# VoiceInterface.net
KiCad netlist of a schematic drawn in EAGLE
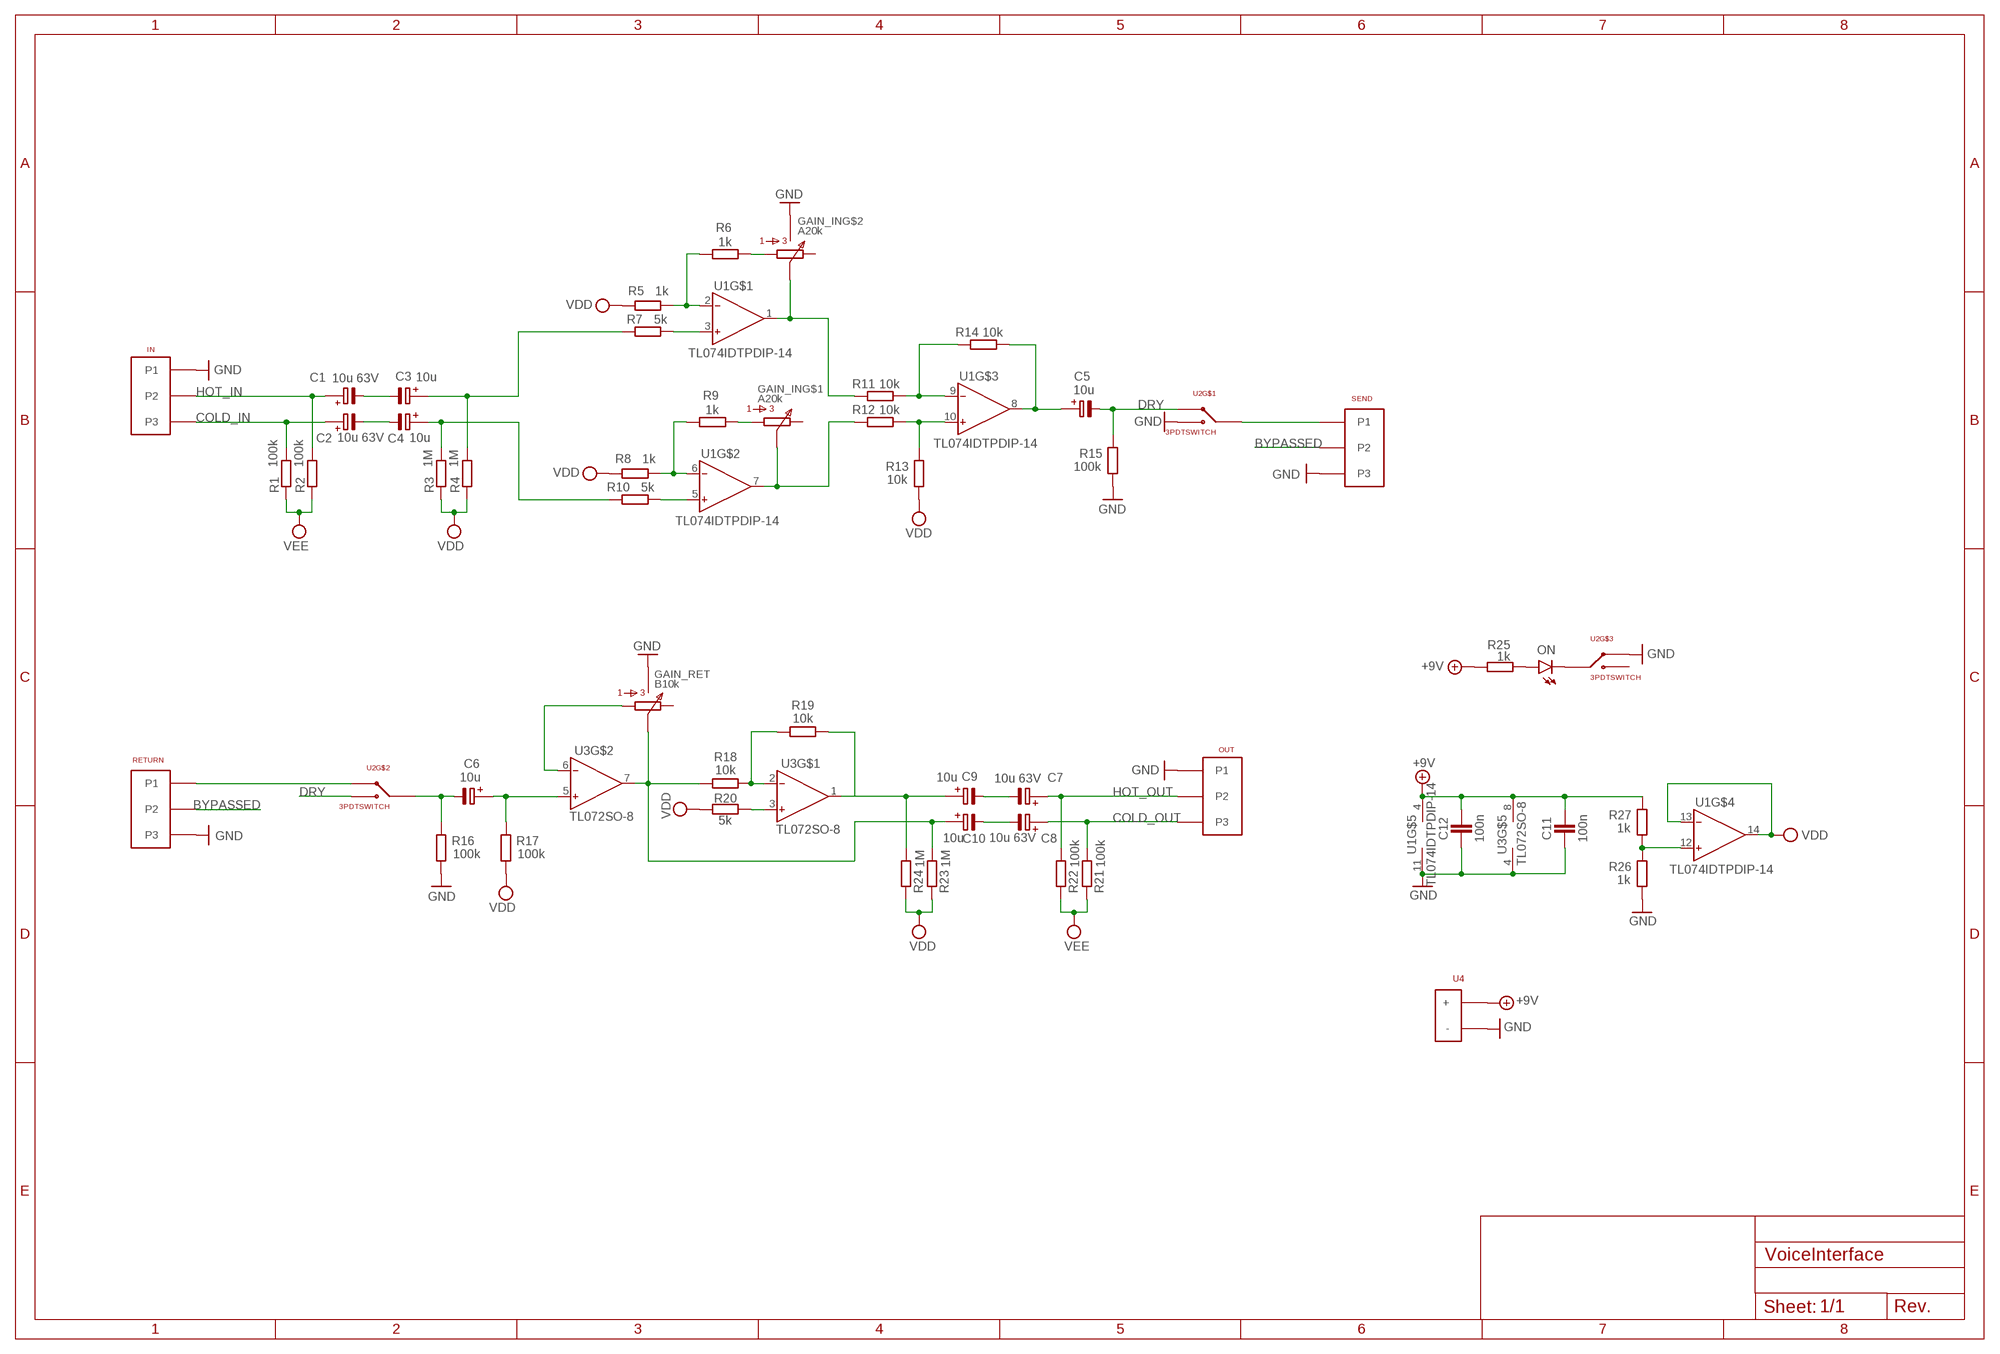
[diagram p0: schematic, sheet 1]

(export (version "E")
  (design (tool "Eeschema 10.0.6"))
  (components
    (comp (ref "C1")
      (value "10u 63V")
      (footprint "eagle-import:UD-8X10_NICHICON")
      (libsource (lib "eagle-import") (part "ELECT_CAPACITORCAP10"))
    )
    (comp (ref "C2")
      (value "10u 63V")
      (footprint "eagle-import:UD-8X10_NICHICON")
      (libsource (lib "eagle-import") (part "ELECT_CAPACITORCAP10"))
    )
    (comp (ref "C3")
      (value "10u")
      (footprint "eagle-import:UD-4X5,8_NICHICON")
      (libsource (lib "eagle-import") (part "ELECT_CAPACITORCAP6"))
    )
    (comp (ref "C4")
      (value "10u")
      (footprint "eagle-import:UD-4X5,8_NICHICON")
      (libsource (lib "eagle-import") (part "ELECT_CAPACITORCAP6"))
    )
    (comp (ref "C5")
      (value "10u")
      (footprint "eagle-import:UD-4X5,8_NICHICON")
      (libsource (lib "eagle-import") (part "ELECT_CAPACITORCAP6"))
    )
    (comp (ref "C6")
      (value "10u")
      (footprint "eagle-import:UD-4X5,8_NICHICON")
      (libsource (lib "eagle-import") (part "ELECT_CAPACITORCAP6"))
    )
    (comp (ref "C7")
      (value "10u 63V")
      (footprint "eagle-import:UD-8X10_NICHICON")
      (libsource (lib "eagle-import") (part "ELECT_CAPACITORCAP10"))
    )
    (comp (ref "C8")
      (value "10u 63V")
      (footprint "eagle-import:UD-8X10_NICHICON")
      (libsource (lib "eagle-import") (part "ELECT_CAPACITORCAP10"))
    )
    (comp (ref "C9")
      (value "10u")
      (footprint "eagle-import:UD-4X5,8_NICHICON")
      (libsource (lib "eagle-import") (part "ELECT_CAPACITORCAP6"))
    )
    (comp (ref "C10")
      (value "10u")
      (footprint "eagle-import:UD-4X5,8_NICHICON")
      (libsource (lib "eagle-import") (part "ELECT_CAPACITORCAP6"))
    )
    (comp (ref "C11")
      (value "100n")
      (footprint "eagle-import:0603")
      (libsource (lib "eagle-import") (part "CAPACITORC-0603"))
    )
    (comp (ref "C12")
      (value "100n")
      (footprint "eagle-import:0603")
      (libsource (lib "eagle-import") (part "CAPACITORC-0603"))
    )
    (comp (ref "GAIN_IN")
      (value "A20k")
      (footprint "eagle-import:P0925N")
      (fields (field (name "MPN") "P0925N-FC20AR100K"))
      (libsource (lib "eagle-import") (part "STEREO_POT"))
    )
    (comp (ref "GAIN_RET")
      (value "B10k")
      (footprint "eagle-import:P0915N")
      (fields (field (name "MPN") "P0915N-QC15AR100K"))
      (libsource (lib "eagle-import") (part "POT"))
    )
    (comp (ref "IN")
      (value "3_PIN_PORT")
      (footprint "eagle-import:3_PIN_PORT")
      (libsource (lib "eagle-import") (part "3_PIN_PORT"))
    )
    (comp (ref "ON")
      (value "LEDLED_THROUGH")
      (footprint "eagle-import:LED3MM")
      (libsource (lib "eagle-import") (part "LEDLED_THROUGH"))
    )
    (comp (ref "OUT")
      (value "3_PIN_PORT")
      (footprint "eagle-import:3_PIN_PORT")
      (libsource (lib "eagle-import") (part "3_PIN_PORT"))
    )
    (comp (ref "R1")
      (value "100k")
      (footprint "eagle-import:R0603")
      (libsource (lib "eagle-import") (part "RESISTOR"))
    )
    (comp (ref "R2")
      (value "100k")
      (footprint "eagle-import:R0603")
      (libsource (lib "eagle-import") (part "RESISTOR"))
    )
    (comp (ref "R3")
      (value "1M")
      (footprint "eagle-import:R0603")
      (libsource (lib "eagle-import") (part "RESISTOR"))
    )
    (comp (ref "R4")
      (value "1M")
      (footprint "eagle-import:R0603")
      (libsource (lib "eagle-import") (part "RESISTOR"))
    )
    (comp (ref "R5")
      (value "1k")
      (footprint "eagle-import:R0603")
      (libsource (lib "eagle-import") (part "RESISTOR"))
    )
    (comp (ref "R6")
      (value "1k")
      (footprint "eagle-import:R0603")
      (libsource (lib "eagle-import") (part "RESISTOR"))
    )
    (comp (ref "R7")
      (value "5k")
      (footprint "eagle-import:R0603")
      (libsource (lib "eagle-import") (part "RESISTOR"))
    )
    (comp (ref "R8")
      (value "1k")
      (footprint "eagle-import:R0603")
      (libsource (lib "eagle-import") (part "RESISTOR"))
    )
    (comp (ref "R9")
      (value "1k")
      (footprint "eagle-import:R0603")
      (libsource (lib "eagle-import") (part "RESISTOR"))
    )
    (comp (ref "R10")
      (value "5k")
      (footprint "eagle-import:R0603")
      (libsource (lib "eagle-import") (part "RESISTOR"))
    )
    (comp (ref "R11")
      (value "10k")
      (footprint "eagle-import:R0603")
      (libsource (lib "eagle-import") (part "RESISTOR"))
    )
    (comp (ref "R12")
      (value "10k")
      (footprint "eagle-import:R0603")
      (libsource (lib "eagle-import") (part "RESISTOR"))
    )
    (comp (ref "R13")
      (value "10k")
      (footprint "eagle-import:R0603")
      (libsource (lib "eagle-import") (part "RESISTOR"))
    )
    (comp (ref "R14")
      (value "10k")
      (footprint "eagle-import:R0603")
      (libsource (lib "eagle-import") (part "RESISTOR"))
    )
    (comp (ref "R15")
      (value "100k")
      (footprint "eagle-import:R0603")
      (libsource (lib "eagle-import") (part "RESISTOR"))
    )
    (comp (ref "R16")
      (value "100k")
      (footprint "eagle-import:R0603")
      (libsource (lib "eagle-import") (part "RESISTOR"))
    )
    (comp (ref "R17")
      (value "100k")
      (footprint "eagle-import:R0603")
      (libsource (lib "eagle-import") (part "RESISTOR"))
    )
    (comp (ref "R18")
      (value "10k")
      (footprint "eagle-import:R0603")
      (libsource (lib "eagle-import") (part "RESISTOR"))
    )
    (comp (ref "R19")
      (value "10k")
      (footprint "eagle-import:R0603")
      (libsource (lib "eagle-import") (part "RESISTOR"))
    )
    (comp (ref "R20")
      (value "5k")
      (footprint "eagle-import:R0603")
      (libsource (lib "eagle-import") (part "RESISTOR"))
    )
    (comp (ref "R21")
      (value "100k")
      (footprint "eagle-import:R0603")
      (libsource (lib "eagle-import") (part "RESISTOR"))
    )
    (comp (ref "R22")
      (value "100k")
      (footprint "eagle-import:R0603")
      (libsource (lib "eagle-import") (part "RESISTOR"))
    )
    (comp (ref "R23")
      (value "1M")
      (footprint "eagle-import:R0603")
      (libsource (lib "eagle-import") (part "RESISTOR"))
    )
    (comp (ref "R24")
      (value "1M")
      (footprint "eagle-import:R0603")
      (libsource (lib "eagle-import") (part "RESISTOR"))
    )
    (comp (ref "R25")
      (value "1k")
      (footprint "eagle-import:R0603")
      (libsource (lib "eagle-import") (part "RESISTOR"))
    )
    (comp (ref "R26")
      (value "1k")
      (footprint "eagle-import:R0603")
      (libsource (lib "eagle-import") (part "RESISTOR"))
    )
    (comp (ref "R27")
      (value "1k")
      (footprint "eagle-import:R0603")
      (libsource (lib "eagle-import") (part "RESISTOR"))
    )
    (comp (ref "RETURN")
      (value "3_PIN_PORT")
      (footprint "eagle-import:3_PIN_PORT")
      (libsource (lib "eagle-import") (part "3_PIN_PORT"))
    )
    (comp (ref "SEND")
      (value "3_PIN_PORT")
      (footprint "eagle-import:3_PIN_PORT")
      (libsource (lib "eagle-import") (part "3_PIN_PORT"))
    )
    (comp (ref "U1")
      (value "TL074IDTPDIP-14")
      (footprint "eagle-import:DIP762W53P254L1969H508Q14B")
      (fields (field (name "MPN") "TL074CN"))
      (libsource (lib "eagle-import") (part "library_TL074IDTPDIP-14"))
    )
    (comp (ref "U2")
      (value "3PDTSWITCH")
      (footprint "eagle-import:FS57003PLT2B2M1QE")
      (fields (field (name "MPN") "FS57003PLT2B2M1QE"))
      (libsource (lib "eagle-import") (part "3PDTSWITCH"))
    )
    (comp (ref "U3")
      (value "TL072SO-8")
      (footprint "eagle-import:SOIC127P600X175-8N")
      (libsource (lib "eagle-import") (part "TL072SO-8"))
    )
    (comp (ref "U4")
      (value "POWER")
      (footprint "eagle-import:POWER")
      (libsource (lib "eagle-import") (part "POWER"))
    )
  )
  (nets
    (net (code "1") (name "+9V") (class "Default")
      (node (ref "C11") (pin "2") (pinfunction "2_2") (pintype "passive"))
      (node (ref "C12") (pin "2") (pinfunction "2_2") (pintype "passive"))
      (node (ref "R25") (pin "2") (pinfunction "2_2") (pintype "passive"))
      (node (ref "R27") (pin "1") (pinfunction "1_1") (pintype "passive"))
      (node (ref "U1") (pin "4") (pinfunction "V+_4") (pintype "power_in"))
      (node (ref "U3") (pin "8") (pinfunction "V+_8") (pintype "power_in"))
      (node (ref "U4") (pin "P$1") (pinfunction "+_P$1") (pintype "power_in"))
    )
    (net (code "2") (name "/BYPASSED") (class "Default")
      (node (ref "RETURN") (pin "P$2") (pinfunction "P2_P$2") (pintype "bidirectional"))
      (node (ref "SEND") (pin "P$2") (pinfunction "P2_P$2") (pintype "bidirectional"))
    )
    (net (code "3") (name "/COLD_IN") (class "Default")
      (node (ref "C2") (pin "+") (pinfunction "+_+") (pintype "passive"))
      (node (ref "IN") (pin "P$3") (pinfunction "P3_P$3") (pintype "bidirectional"))
      (node (ref "R1") (pin "2") (pinfunction "2_2") (pintype "passive"))
    )
    (net (code "4") (name "/COLD_OUT") (class "Default")
      (node (ref "C8") (pin "+") (pinfunction "+_+") (pintype "passive"))
      (node (ref "OUT") (pin "P$3") (pinfunction "P3_P$3") (pintype "bidirectional"))
      (node (ref "R21") (pin "2") (pinfunction "2_2") (pintype "passive"))
    )
    (net (code "5") (name "/DRY") (class "Default")
      (node (ref "C5") (pin "-") (pinfunction "-_-") (pintype "passive"))
      (node (ref "R15") (pin "1") (pinfunction "1_1") (pintype "passive"))
      (node (ref "U2") (pin "P$1") (pinfunction "1_P$1") (pintype "bidirectional"))
      (node (ref "U2") (pin "P$6") (pinfunction "3_P$6") (pintype "bidirectional"))
    )
    (net (code "6") (name "/HOT_IN") (class "Default")
      (node (ref "C1") (pin "+") (pinfunction "+_+") (pintype "passive"))
      (node (ref "IN") (pin "P$2") (pinfunction "P2_P$2") (pintype "bidirectional"))
      (node (ref "R2") (pin "2") (pinfunction "2_2") (pintype "passive"))
    )
    (net (code "7") (name "/HOT_OUT") (class "Default")
      (node (ref "C7") (pin "+") (pinfunction "+_+") (pintype "passive"))
      (node (ref "OUT") (pin "P$2") (pinfunction "P2_P$2") (pintype "bidirectional"))
      (node (ref "R22") (pin "2") (pinfunction "2_2") (pintype "passive"))
    )
    (net (code "8") (name "GND") (class "Default")
      (node (ref "C11") (pin "1") (pinfunction "1_1") (pintype "passive"))
      (node (ref "C12") (pin "1") (pinfunction "1_1") (pintype "passive"))
      (node (ref "GAIN_IN") (pin "P$7") (pinfunction "P$1_P$7") (pintype "bidirectional"))
      (node (ref "GAIN_IN") (pin "P$8") (pinfunction "P$1_P$8") (pintype "bidirectional"))
      (node (ref "GAIN_RET") (pin "P$7") (pinfunction "P$1_P$7") (pintype "bidirectional"))
      (node (ref "GAIN_RET") (pin "P$8") (pinfunction "P$1_P$8") (pintype "bidirectional"))
      (node (ref "IN") (pin "P$1") (pinfunction "P1_P$1") (pintype "bidirectional"))
      (node (ref "OUT") (pin "P$1") (pinfunction "P1_P$1") (pintype "bidirectional"))
      (node (ref "R15") (pin "2") (pinfunction "2_2") (pintype "passive"))
      (node (ref "R16") (pin "2") (pinfunction "2_2") (pintype "passive"))
      (node (ref "R26") (pin "2") (pinfunction "2_2") (pintype "passive"))
      (node (ref "RETURN") (pin "P$3") (pinfunction "P3_P$3") (pintype "bidirectional"))
      (node (ref "SEND") (pin "P$3") (pinfunction "P3_P$3") (pintype "bidirectional"))
      (node (ref "U1") (pin "11") (pinfunction "V-_11") (pintype "power_in"))
      (node (ref "U2") (pin "P$3") (pinfunction "3_P$3") (pintype "bidirectional"))
      (node (ref "U2") (pin "P$7") (pinfunction "1_P$7") (pintype "bidirectional"))
      (node (ref "U3") (pin "4") (pinfunction "V-_4") (pintype "power_in"))
      (node (ref "U4") (pin "P$2") (pinfunction "-_P$2") (pintype "power_in"))
    )
    (net (code "9") (name "Net-(C1-Pad-)") (class "Default")
      (node (ref "C1") (pin "-") (pinfunction "-_-") (pintype "passive"))
      (node (ref "C3") (pin "-") (pinfunction "-_-") (pintype "passive"))
    )
    (net (code "10") (name "Net-(C2-Pad-)") (class "Default")
      (node (ref "C2") (pin "-") (pinfunction "-_-") (pintype "passive"))
      (node (ref "C4") (pin "-") (pinfunction "-_-") (pintype "passive"))
    )
    (net (code "11") (name "Net-(C3-Pad+)") (class "Default")
      (node (ref "C3") (pin "+") (pinfunction "+_+") (pintype "passive"))
      (node (ref "R4") (pin "2") (pinfunction "2_2") (pintype "passive"))
      (node (ref "R7") (pin "2") (pinfunction "2_2") (pintype "passive"))
    )
    (net (code "12") (name "Net-(C4-Pad+)") (class "Default")
      (node (ref "C4") (pin "+") (pinfunction "+_+") (pintype "passive"))
      (node (ref "R10") (pin "2") (pinfunction "2_2") (pintype "passive"))
      (node (ref "R3") (pin "2") (pinfunction "2_2") (pintype "passive"))
    )
    (net (code "13") (name "Net-(C7-Pad-)") (class "Default")
      (node (ref "C7") (pin "-") (pinfunction "-_-") (pintype "passive"))
      (node (ref "C9") (pin "-") (pinfunction "-_-") (pintype "passive"))
    )
    (net (code "14") (name "Net-(C10-Pad-)") (class "Default")
      (node (ref "C10") (pin "-") (pinfunction "-_-") (pintype "passive"))
      (node (ref "C8") (pin "-") (pinfunction "-_-") (pintype "passive"))
    )
    (net (code "15") (name "Net-(GAIN_INA-1)") (class "Default")
      (node (ref "GAIN_IN") (pin "P$1") (pinfunction "1_P$1") (pintype "passive"))
      (node (ref "R9") (pin "1") (pinfunction "1_1") (pintype "passive"))
    )
    (net (code "16") (name "Net-(GAIN_INA-2)") (class "Default")
      (node (ref "GAIN_IN") (pin "P$2") (pinfunction "2_P$2") (pintype "passive"))
      (node (ref "R12") (pin "2") (pinfunction "2_2") (pintype "passive"))
      (node (ref "U1") (pin "7") (pinfunction "OUT_7") (pintype "output"))
    )
    (net (code "17") (name "Net-(GAIN_INB-1)") (class "Default")
      (node (ref "GAIN_IN") (pin "P$4") (pinfunction "1_P$4") (pintype "passive"))
      (node (ref "R6") (pin "1") (pinfunction "1_1") (pintype "passive"))
    )
    (net (code "18") (name "Net-(GAIN_INB-2)") (class "Default")
      (node (ref "GAIN_IN") (pin "P$5") (pinfunction "2_P$5") (pintype "passive"))
      (node (ref "R11") (pin "2") (pinfunction "2_2") (pintype "passive"))
      (node (ref "U1") (pin "1") (pinfunction "OUT_1") (pintype "output"))
    )
    (net (code "19") (name "Net-(GAIN_RET-1)") (class "Default")
      (node (ref "GAIN_RET") (pin "P$1") (pinfunction "1_P$1") (pintype "passive"))
      (node (ref "U3") (pin "6") (pinfunction "IN-_6") (pintype "input"))
    )
    (net (code "20") (name "Net-(GAIN_RET-2)") (class "Default")
      (node (ref "C10") (pin "+") (pinfunction "+_+") (pintype "passive"))
      (node (ref "GAIN_RET") (pin "P$2") (pinfunction "2_P$2") (pintype "passive"))
      (node (ref "R18") (pin "2") (pinfunction "2_2") (pintype "passive"))
      (node (ref "R23") (pin "2") (pinfunction "2_2") (pintype "passive"))
      (node (ref "U3") (pin "7") (pinfunction "OUT_7") (pintype "output"))
    )
    (net (code "21") (name "Net-(ON-C)") (class "Default")
      (node (ref "ON") (pin "K") (pinfunction "C_K") (pintype "passive"))
      (node (ref "U2") (pin "P$8") (pinfunction "2_P$8") (pintype "bidirectional"))
    )
    (net (code "22") (name "Net-(ON-PadA)") (class "Default")
      (node (ref "ON") (pin "A") (pinfunction "A_A") (pintype "passive"))
      (node (ref "R25") (pin "1") (pinfunction "1_1") (pintype "passive"))
    )
    (net (code "23") (name "Net-(RETURN-P1)") (class "Default")
      (node (ref "RETURN") (pin "P$1") (pinfunction "P1_P$1") (pintype "bidirectional"))
      (node (ref "U2") (pin "P$4") (pinfunction "1_P$4") (pintype "bidirectional"))
    )
    (net (code "24") (name "Net-(SEND-P1)") (class "Default")
      (node (ref "SEND") (pin "P$1") (pinfunction "P1_P$1") (pintype "bidirectional"))
      (node (ref "U2") (pin "P$2") (pinfunction "2_P$2") (pintype "bidirectional"))
    )
    (net (code "25") (name "Net-(U1A-IN+)") (class "Default")
      (node (ref "R7") (pin "1") (pinfunction "1_1") (pintype "passive"))
      (node (ref "U1") (pin "3") (pinfunction "IN+_3") (pintype "input"))
    )
    (net (code "26") (name "Net-(U1A-IN-)") (class "Default")
      (node (ref "R5") (pin "1") (pinfunction "1_1") (pintype "passive"))
      (node (ref "R6") (pin "2") (pinfunction "2_2") (pintype "passive"))
      (node (ref "U1") (pin "2") (pinfunction "IN-_2") (pintype "input"))
    )
    (net (code "27") (name "Net-(U1B-IN+)") (class "Default")
      (node (ref "R10") (pin "1") (pinfunction "1_1") (pintype "passive"))
      (node (ref "U1") (pin "5") (pinfunction "IN+_5") (pintype "input"))
    )
    (net (code "28") (name "Net-(U1B-IN-)") (class "Default")
      (node (ref "R8") (pin "1") (pinfunction "1_1") (pintype "passive"))
      (node (ref "R9") (pin "2") (pinfunction "2_2") (pintype "passive"))
      (node (ref "U1") (pin "6") (pinfunction "IN-_6") (pintype "input"))
    )
    (net (code "29") (name "Net-(U1C-IN+)") (class "Default")
      (node (ref "R12") (pin "1") (pinfunction "1_1") (pintype "passive"))
      (node (ref "R13") (pin "1") (pinfunction "1_1") (pintype "passive"))
      (node (ref "U1") (pin "10") (pinfunction "IN+_10") (pintype "input"))
    )
    (net (code "30") (name "Net-(U1C-IN-)") (class "Default")
      (node (ref "R11") (pin "1") (pinfunction "1_1") (pintype "passive"))
      (node (ref "R14") (pin "2") (pinfunction "2_2") (pintype "passive"))
      (node (ref "U1") (pin "9") (pinfunction "IN-_9") (pintype "input"))
    )
    (net (code "31") (name "Net-(U1C-OUT)") (class "Default")
      (node (ref "C5") (pin "+") (pinfunction "+_+") (pintype "passive"))
      (node (ref "R14") (pin "1") (pinfunction "1_1") (pintype "passive"))
      (node (ref "U1") (pin "8") (pinfunction "OUT_8") (pintype "output"))
    )
    (net (code "32") (name "Net-(U1D-IN+)") (class "Default")
      (node (ref "R26") (pin "1") (pinfunction "1_1") (pintype "passive"))
      (node (ref "R27") (pin "2") (pinfunction "2_2") (pintype "passive"))
      (node (ref "U1") (pin "12") (pinfunction "IN+_12") (pintype "input"))
    )
    (net (code "33") (name "Net-(U2B-2)") (class "Default")
      (node (ref "C6") (pin "-") (pinfunction "-_-") (pintype "passive"))
      (node (ref "R16") (pin "1") (pinfunction "1_1") (pintype "passive"))
      (node (ref "U2") (pin "P$5") (pinfunction "2_P$5") (pintype "bidirectional"))
    )
    (net (code "34") (name "Net-(U3A-IN+)") (class "Default")
      (node (ref "R20") (pin "1") (pinfunction "1_1") (pintype "passive"))
      (node (ref "U3") (pin "3") (pinfunction "IN+_3") (pintype "input"))
    )
    (net (code "35") (name "Net-(U3A-IN-)") (class "Default")
      (node (ref "R18") (pin "1") (pinfunction "1_1") (pintype "passive"))
      (node (ref "R19") (pin "2") (pinfunction "2_2") (pintype "passive"))
      (node (ref "U3") (pin "2") (pinfunction "IN-_2") (pintype "input"))
    )
    (net (code "36") (name "Net-(U3A-OUT)") (class "Default")
      (node (ref "C9") (pin "+") (pinfunction "+_+") (pintype "passive"))
      (node (ref "R19") (pin "1") (pinfunction "1_1") (pintype "passive"))
      (node (ref "R24") (pin "2") (pinfunction "2_2") (pintype "passive"))
      (node (ref "U3") (pin "1") (pinfunction "OUT_1") (pintype "output"))
    )
    (net (code "37") (name "Net-(U3B-IN+)") (class "Default")
      (node (ref "C6") (pin "+") (pinfunction "+_+") (pintype "passive"))
      (node (ref "R17") (pin "1") (pinfunction "1_1") (pintype "passive"))
      (node (ref "U3") (pin "5") (pinfunction "IN+_5") (pintype "input"))
    )
    (net (code "38") (name "VDD") (class "Default")
      (node (ref "R13") (pin "2") (pinfunction "2_2") (pintype "passive"))
      (node (ref "R17") (pin "2") (pinfunction "2_2") (pintype "passive"))
      (node (ref "R20") (pin "2") (pinfunction "2_2") (pintype "passive"))
      (node (ref "R23") (pin "1") (pinfunction "1_1") (pintype "passive"))
      (node (ref "R24") (pin "1") (pinfunction "1_1") (pintype "passive"))
      (node (ref "R3") (pin "1") (pinfunction "1_1") (pintype "passive"))
      (node (ref "R4") (pin "1") (pinfunction "1_1") (pintype "passive"))
      (node (ref "R5") (pin "2") (pinfunction "2_2") (pintype "passive"))
      (node (ref "R8") (pin "2") (pinfunction "2_2") (pintype "passive"))
      (node (ref "U1") (pin "13") (pinfunction "IN-_13") (pintype "input"))
      (node (ref "U1") (pin "14") (pinfunction "OUT_14") (pintype "output"))
    )
    (net (code "39") (name "VEE") (class "Default")
      (node (ref "R1") (pin "1") (pinfunction "1_1") (pintype "passive"))
      (node (ref "R2") (pin "1") (pinfunction "1_1") (pintype "passive"))
      (node (ref "R21") (pin "1") (pinfunction "1_1") (pintype "passive"))
      (node (ref "R22") (pin "1") (pinfunction "1_1") (pintype "passive"))
    )
    (net (code "40") (name "unconnected-(GAIN_INA-3-PadP$3)") (class "Default")
      (node (ref "GAIN_IN") (pin "P$3") (pinfunction "3_P$3") (pintype "passive"))
    )
    (net (code "41") (name "unconnected-(GAIN_INB-3-PadP$6)") (class "Default")
      (node (ref "GAIN_IN") (pin "P$6") (pinfunction "3_P$6") (pintype "passive"))
    )
    (net (code "42") (name "unconnected-(GAIN_RET-3-PadP$3)") (class "Default")
      (node (ref "GAIN_RET") (pin "P$3") (pinfunction "3_P$3") (pintype "passive"))
    )
    (net (code "43") (name "unconnected-(U2C-3-PadP$9)") (class "Default")
      (node (ref "U2") (pin "P$9") (pinfunction "3_P$9") (pintype "bidirectional"))
    )
  )
)
